# Analog_Buffer.net
KiCad netlist of a schematic drawn in Altium Designer
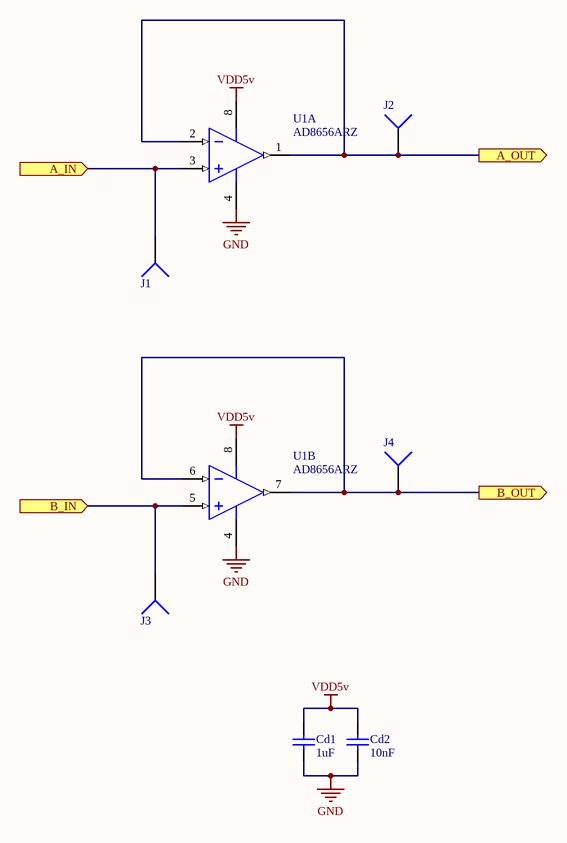
[diagram p0: Analog_Buffer.SchDoc]

(export (version "E")
  (design (tool "Eeschema 10.0.6"))
  (components
    (comp (ref "Cd1")
      (value "1uF")
      (footprint "1608[0603]")
      (description "Capacitor")
      (fields (field (name "Comment") "Cap") (field (name "PUBLISHER") "Altium Limited"))
      (libsource (lib "Miscellaneous Devices") (part "Cap"))
    )
    (comp (ref "Cd2")
      (value "10nF")
      (footprint "1608[0603]")
      (description "Capacitor")
      (fields (field (name "Comment") "Cap") (field (name "PUBLISHER") "Altium Limited"))
      (libsource (lib "Miscellaneous Devices") (part "Cap"))
    )
    (comp (ref "J1")
      (value "Socket")
      (footprint "PIN1")
      (fields (field (name "PUBLISHER") "Altium Limited"))
      (libsource (lib "Miscellaneous Connectors") (part "Socket"))
    )
    (comp (ref "J2")
      (value "Socket")
      (footprint "PIN1")
      (fields (field (name "PUBLISHER") "Altium Limited"))
      (libsource (lib "Miscellaneous Connectors") (part "Socket"))
    )
    (comp (ref "J3")
      (value "Socket")
      (footprint "PIN1")
      (fields (field (name "PUBLISHER") "Altium Limited"))
      (libsource (lib "Miscellaneous Connectors") (part "Socket"))
    )
    (comp (ref "J4")
      (value "Socket")
      (footprint "PIN1")
      (fields (field (name "PUBLISHER") "Altium Limited"))
      (libsource (lib "Miscellaneous Connectors") (part "Socket"))
    )
    (comp (ref "U1")
      (value "AD8656ARZ")
      (footprint "ADI-R-8_N")
      (fields (field (name "GENERIC PART NUMBER") "AD8656") (field (name "MANUFACTURER") "Analog Devices"))
      (libsource (lib "Analog Devices Operational Amplifiers") (part "AD8656ARZ"))
    )
  )
  (nets
    (net (code "1") (name "/A_IN") (class "Default")
      (node (ref "J1") (pin "1") (pinfunction "1_1") (pintype "passive"))
      (node (ref "U1") (pin "3") (pinfunction "+IN_A_3") (pintype "input"))
    )
    (net (code "2") (name "/A_OUT") (class "Default")
      (node (ref "J2") (pin "1") (pinfunction "1_1") (pintype "passive"))
      (node (ref "U1") (pin "1") (pinfunction "OUT_A_1") (pintype "output"))
      (node (ref "U1") (pin "2") (pinfunction "-IN_A_2") (pintype "input"))
    )
    (net (code "3") (name "/B_IN") (class "Default")
      (node (ref "J3") (pin "1") (pinfunction "1_1") (pintype "passive"))
      (node (ref "U1") (pin "5") (pinfunction "+IN_B_5") (pintype "input"))
    )
    (net (code "4") (name "/B_OUT") (class "Default")
      (node (ref "J4") (pin "1") (pinfunction "1_1") (pintype "passive"))
      (node (ref "U1") (pin "6") (pinfunction "-IN_B_6") (pintype "input"))
      (node (ref "U1") (pin "7") (pinfunction "OUT_B_7") (pintype "output"))
    )
    (net (code "5") (name "GND") (class "Default")
      (node (ref "Cd1") (pin "2") (pinfunction "2_2") (pintype "passive"))
      (node (ref "Cd2") (pin "2") (pinfunction "2_2") (pintype "passive"))
      (node (ref "U1") (pin "4") (pinfunction "-V_4") (pintype "power_in"))
    )
    (net (code "6") (name "VDD5v") (class "Default")
      (node (ref "Cd1") (pin "1") (pinfunction "1_1") (pintype "passive"))
      (node (ref "Cd2") (pin "1") (pinfunction "1_1") (pintype "passive"))
      (node (ref "U1") (pin "8") (pinfunction "+V_8") (pintype "power_in"))
    )
  )
)
